# S4_MAF_Adapter.net
KiCad netlist of a schematic drawn in EAGLE
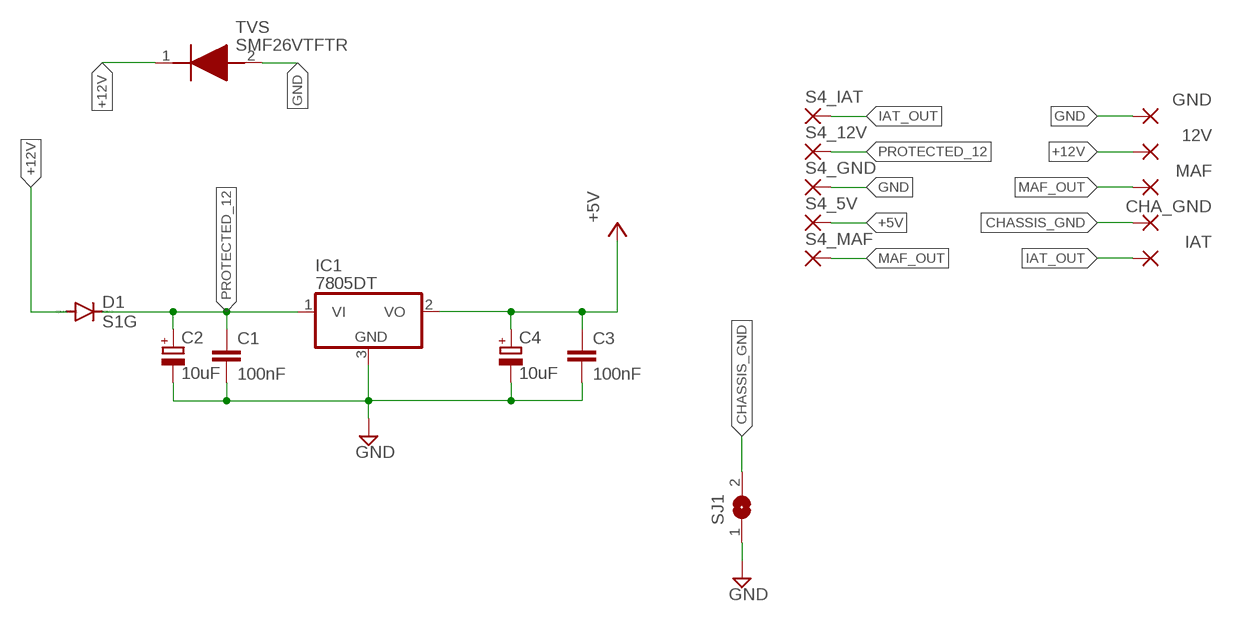
[diagram p0: schematic, sheet 1]

(export (version "E")
  (design (tool "Eeschema 10.0.6"))
  (components
    (comp (ref "12V")
      (value "2,54/1,1")
      (footprint "eagle-import:2,54_1,1")
      (libsource (lib "eagle-import") (part "2,54/1,1"))
    )
    (comp (ref "C1")
      (value "100nF")
      (footprint "eagle-import:C0805")
      (libsource (lib "eagle-import") (part "C-EUC0805"))
    )
    (comp (ref "C2")
      (value "10uF")
      (footprint "eagle-import:E2-5")
      (libsource (lib "eagle-import") (part "CPOL-EUE2-5"))
    )
    (comp (ref "C3")
      (value "100nF")
      (footprint "eagle-import:C0805")
      (libsource (lib "eagle-import") (part "C-EUC0805"))
    )
    (comp (ref "C4")
      (value "10uF")
      (footprint "eagle-import:E2-5")
      (libsource (lib "eagle-import") (part "CPOL-EUE2-5"))
    )
    (comp (ref "CHA_GND")
      (value "2,54/1,1")
      (footprint "eagle-import:2,54_1,1")
      (libsource (lib "eagle-import") (part "2,54/1,1"))
    )
    (comp (ref "D1")
      (value "S1G")
      (footprint "eagle-import:DO-214AC")
      (libsource (lib "eagle-import") (part "DIODE-DO-214AC"))
    )
    (comp (ref "GND")
      (value "2,54/1,1")
      (footprint "eagle-import:2,54_1,1")
      (libsource (lib "eagle-import") (part "2,54/1,1"))
    )
    (comp (ref "IAT")
      (value "2,54/1,1")
      (footprint "eagle-import:2,54_1,1")
      (libsource (lib "eagle-import") (part "2,54/1,1"))
    )
    (comp (ref "IC1")
      (value "7805DT")
      (footprint "eagle-import:TO252")
      (libsource (lib "eagle-import") (part "78DT05"))
    )
    (comp (ref "MAF")
      (value "2,54/1,1")
      (footprint "eagle-import:2,54_1,1")
      (libsource (lib "eagle-import") (part "2,54/1,1"))
    )
    (comp (ref "S4_5V")
      (value "2,54/1,1")
      (footprint "eagle-import:2,54_1,1")
      (libsource (lib "eagle-import") (part "2,54/1,1"))
    )
    (comp (ref "S4_12V")
      (value "2,54/1,1")
      (footprint "eagle-import:2,54_1,1")
      (libsource (lib "eagle-import") (part "2,54/1,1"))
    )
    (comp (ref "S4_GND")
      (value "2,54/1,1")
      (footprint "eagle-import:2,54_1,1")
      (libsource (lib "eagle-import") (part "2,54/1,1"))
    )
    (comp (ref "S4_IAT")
      (value "2,54/1,1")
      (footprint "eagle-import:2,54_1,1")
      (libsource (lib "eagle-import") (part "2,54/1,1"))
    )
    (comp (ref "S4_MAF")
      (value "2,54/1,1")
      (footprint "eagle-import:2,54_1,1")
      (libsource (lib "eagle-import") (part "2,54/1,1"))
    )
    (comp (ref "SJ1") (value "SJ") (footprint "eagle-import:SJ") (libsource (lib "eagle-import") (part "SJ")))
    (comp (ref "TVS")
      (value "SMF26VTFTR")
      (footprint "eagle-import:SMF26VTFTR")
      (fields (field (name "MOUSER_PART_NUMBER") "755-SMF26VTFTR"))
      (libsource (lib "eagle-import") (part "SMF26VTFTR"))
    )
  )
  (nets
    (net (code "1") (name "+5V") (class "Default")
      (node (ref "C3") (pin "1") (pinfunction "1_1") (pintype "passive"))
      (node (ref "C4") (pin "+") (pinfunction "+_+") (pintype "passive"))
      (node (ref "IC1") (pin "2") (pinfunction "VO_2") (pintype "passive"))
      (node (ref "S4_5V") (pin "1") (pinfunction "P_1") (pintype "passive"))
    )
    (net (code "2") (name "+12V") (class "Default")
      (node (ref "12V") (pin "1") (pinfunction "P_1") (pintype "passive"))
      (node (ref "D1") (pin "A") (pinfunction "A_A") (pintype "passive"))
      (node (ref "TVS") (pin "1") (pinfunction "K_1") (pintype "bidirectional"))
    )
    (net (code "3") (name "CHASSIS_GND") (class "Default")
      (node (ref "CHA_GND") (pin "1") (pinfunction "P_1") (pintype "passive"))
      (node (ref "SJ1") (pin "2") (pinfunction "2_2") (pintype "passive"))
    )
    (net (code "4") (name "GND") (class "Default")
      (node (ref "C1") (pin "2") (pinfunction "2_2") (pintype "passive"))
      (node (ref "C2") (pin "-") (pinfunction "-_-") (pintype "passive"))
      (node (ref "C3") (pin "2") (pinfunction "2_2") (pintype "passive"))
      (node (ref "C4") (pin "-") (pinfunction "-_-") (pintype "passive"))
      (node (ref "GND") (pin "1") (pinfunction "P_1") (pintype "passive"))
      (node (ref "IC1") (pin "3") (pinfunction "GND_3") (pintype "passive"))
      (node (ref "S4_GND") (pin "1") (pinfunction "P_1") (pintype "passive"))
      (node (ref "SJ1") (pin "1") (pinfunction "1_1") (pintype "passive"))
      (node (ref "TVS") (pin "2") (pinfunction "A_2") (pintype "bidirectional"))
    )
    (net (code "5") (name "IAT_OUT") (class "Default")
      (node (ref "IAT") (pin "1") (pinfunction "P_1") (pintype "passive"))
      (node (ref "S4_IAT") (pin "1") (pinfunction "P_1") (pintype "passive"))
    )
    (net (code "6") (name "MAF_OUT") (class "Default")
      (node (ref "MAF") (pin "1") (pinfunction "P_1") (pintype "passive"))
      (node (ref "S4_MAF") (pin "1") (pinfunction "P_1") (pintype "passive"))
    )
    (net (code "7") (name "PROTECTED_12") (class "Default")
      (node (ref "C1") (pin "1") (pinfunction "1_1") (pintype "passive"))
      (node (ref "C2") (pin "+") (pinfunction "+_+") (pintype "passive"))
      (node (ref "D1") (pin "C") (pinfunction "C_C") (pintype "passive"))
      (node (ref "IC1") (pin "1") (pinfunction "VI_1") (pintype "input"))
      (node (ref "S4_12V") (pin "1") (pinfunction "P_1") (pintype "passive"))
    )
  )
)
